# motordriver-v4_0_stspin.net
KiCad netlist of a schematic drawn in Altium Designer
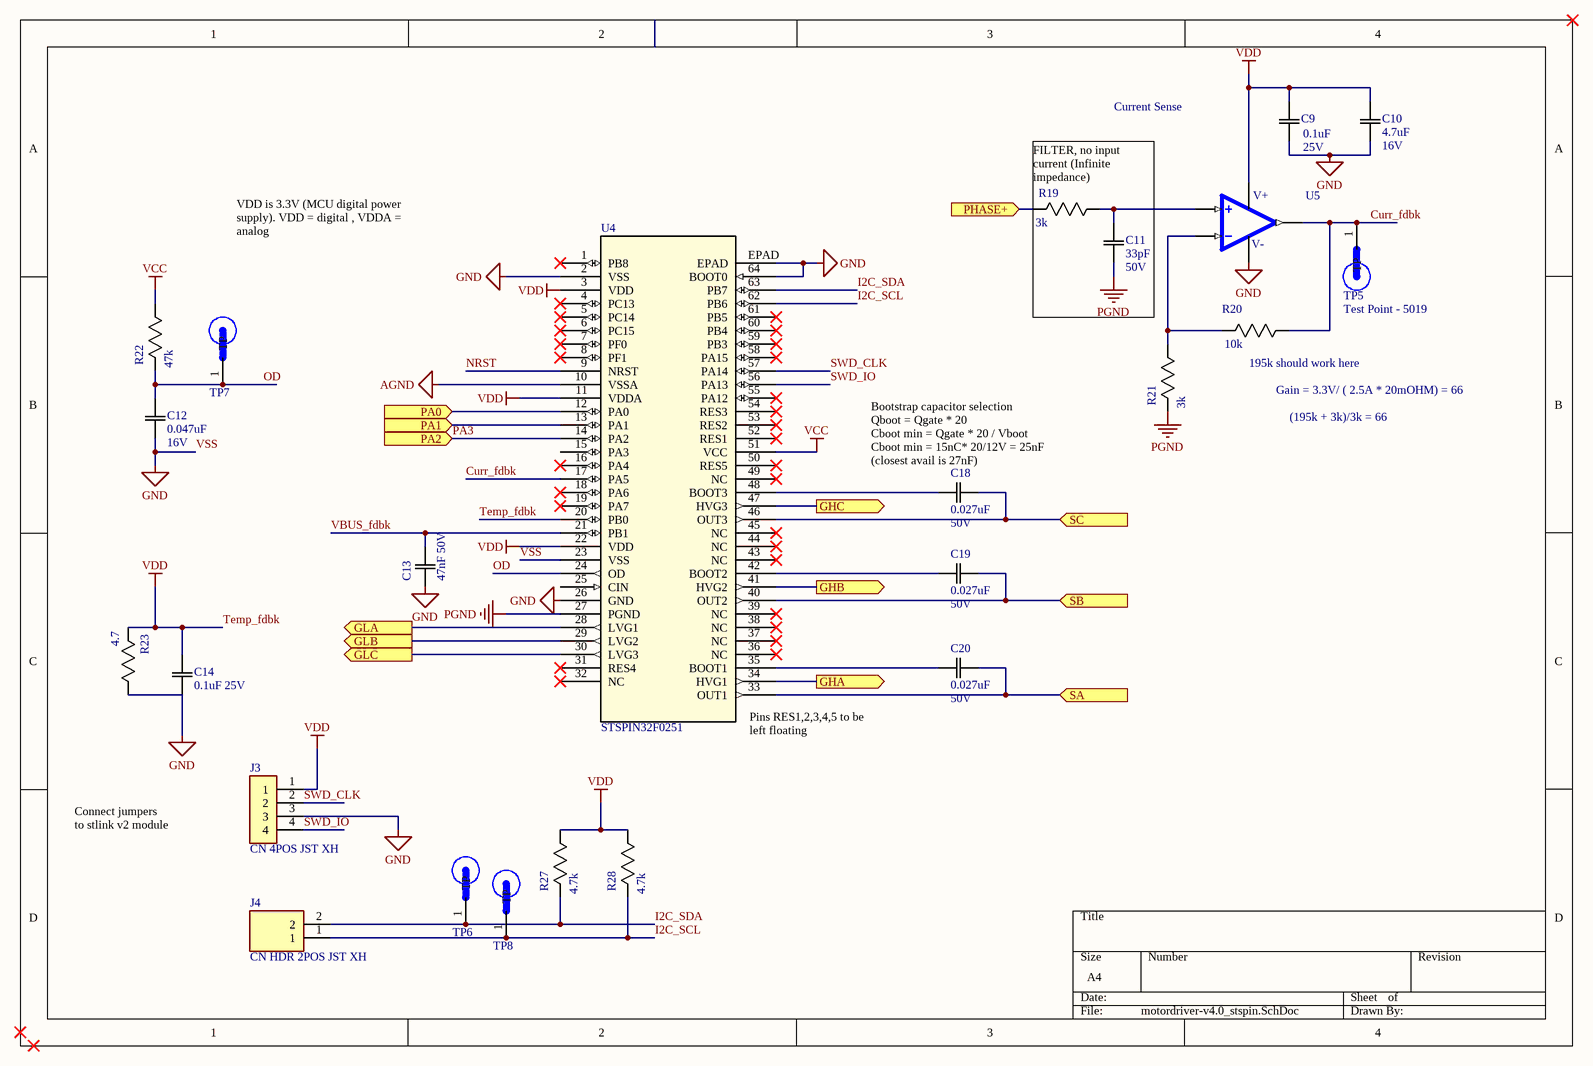
[diagram p0: motordriver-v4.0_stspin.SchDoc]

(export (version "E")
  (design (tool "Eeschema 10.0.6"))
  (components
    (comp (ref "C9")
      (value "0.1uF")
      (footprint "0805")
      (description "CAP CER 0.1UF 25V X7R 0805")
      (fields
        (field (name "TOLERANCE") "10%")
        (field (name "RATING") "25V")
        (field (name "Comment") "0.1uF 25V")
      )
      (libsource (lib "AltiumLibraries") (part "CAP 0.1uF 25V"))
    )
    (comp (ref "C10")
      (value "4.7uF")
      (footprint "0603")
      (description "CAP CER 4.7UF 16V X5R 0603/0805")
      (fields (field (name "TOLERANCE") "10%") (field (name "RATING") "16V"))
      (libsource (lib "AltiumLibraries") (part "CAP 4.7uF 16V"))
    )
    (comp (ref "C11")
      (value "33pF")
      (footprint "0603")
      (description "CAP CER 33PF 50V X7R 0603/0805")
      (fields (field (name "TOLERANCE") "10%") (field (name "RATING") "50V"))
      (libsource (lib "AltiumLibraries") (part "CAP 33pF 50V"))
    )
    (comp (ref "C12")
      (value "0.047uF")
      (footprint "0603")
      (description "CAP CER 0.047UF 16V X5R 0603/0805")
      (fields (field (name "TOLERANCE") "10%") (field (name "RATING") "16V"))
      (libsource (lib "AltiumLibraries") (part "CAP 0.047uF 16V"))
    )
    (comp (ref "C13")
      (value "47nF 50V")
      (footprint "0805")
      (description "CAP CER 0.047UF 50V X7R 0805")
      (fields (field (name "TOLERANCE") "5%"))
      (libsource (lib "AltiumLibraries") (part "CAP 47nF 50V"))
    )
    (comp (ref "C14")
      (value "0.1uF 25V")
      (footprint "0805")
      (description "CAP CER 0.1UF 25V X7R 0805")
      (fields (field (name "TOLERANCE") "10%"))
      (libsource (lib "AltiumLibraries") (part "CAP 0.1uF 25V"))
    )
    (comp (ref "C18")
      (value "0.027uF")
      (footprint "0805")
      (description "CAP CER 0.027UF 50V X7R 0805")
      (fields (field (name "TOLERANCE") "5%") (field (name "RATING") "50V"))
      (libsource (lib "AltiumLibraries") (part "CAP 0.027UF 50V X7R 0805"))
    )
    (comp (ref "C19")
      (value "0.027uF")
      (footprint "0805")
      (description "CAP CER 0.027UF 50V X7R 0805")
      (fields (field (name "TOLERANCE") "5%") (field (name "RATING") "50V"))
      (libsource (lib "AltiumLibraries") (part "CAP 0.027UF 50V X7R 0805"))
    )
    (comp (ref "C20")
      (value "0.027uF")
      (footprint "0805")
      (description "CAP CER 0.027UF 50V X7R 0805")
      (fields (field (name "TOLERANCE") "5%") (field (name "RATING") "50V"))
      (libsource (lib "AltiumLibraries") (part "CAP 0.027UF 50V X7R 0805"))
    )
    (comp (ref "J3")
      (value "CN 4POS JST XH")
      (footprint "JST_B4B-XH-A(LF)(SN)")
      (description "Connector Header Through Hole 4 position 0.098 _2.50mm_\r\nB4B-XH-A(LF)(SN)")
      (fields (field (name "MP") "B4B-XH-A_LF__SN_") (field (name "MF") "JST Sales"))
      (libsource (lib "AltiumLibraries") (part "CN 4POS JST XH"))
    )
    (comp (ref "J4")
      (value "CN HDR 2POS JST XH")
      (footprint "JST_B2B-XH-A(LF)(SN)")
      (description "Connector Header Through Hole 2 position 0.098 _2.50mm_\r\nJST XH")
      (fields (field (name "MP") "B2B-XH-A_LF__SN_") (field (name "MF") "JST Sales"))
      (libsource (lib "AltiumLibraries") (part "CN HDR 2POS JST XH"))
    )
    (comp (ref "R19")
      (value "3k")
      (footprint "0805")
      (description "RES SMD 3K OHM 5% 1/8W 0805")
      (fields (field (name "TOLERANCE") "5%"))
      (libsource (lib "AltiumLibraries") (part "RES 3k 1/8W"))
    )
    (comp (ref "R20")
      (value "10k")
      (footprint "0805")
      (description "RES SMD 10K OHM 5% 1/8W 0805")
      (fields (field (name "TOLERANCE") "5%"))
      (libsource (lib "AltiumLibraries") (part "RES 10k 1/8W - 5%"))
    )
    (comp (ref "R21")
      (value "3k")
      (footprint "0805")
      (description "RES SMD 3K OHM 5% 1/8W 0805")
      (fields (field (name "TOLERANCE") "5%"))
      (libsource (lib "AltiumLibraries") (part "RES 3k 1/8W"))
    )
    (comp (ref "R22")
      (value "47k")
      (footprint "0805")
      (description "RES SMD 47k OHM 5% 1/8W 0805")
      (fields (field (name "TOLERANCE") "5%"))
      (libsource (lib "AltiumLibraries") (part "RES 47k 1/8W - 5%"))
    )
    (comp (ref "R23")
      (value "4.7")
      (footprint "0805")
      (description "RES SMD 4.7 OHM 5% 1/8W 0805")
      (fields (field (name "TOLERANCE") "5%"))
      (libsource (lib "AltiumLibraries") (part "RES 4.7 1/8W"))
    )
    (comp (ref "R27")
      (value "4.7k")
      (footprint "0805")
      (description "RES SMD 4.7k OHM 1% 1/8W 0805")
      (fields (field (name "TOLERANCE") "1%"))
      (libsource (lib "AltiumLibraries") (part "RES 4.7k 1/8W - 1%"))
    )
    (comp (ref "R28")
      (value "4.7k")
      (footprint "0805")
      (description "RES SMD 4.7k OHM 1% 1/8W 0805")
      (fields (field (name "TOLERANCE") "1%"))
      (libsource (lib "AltiumLibraries") (part "RES 4.7k 1/8W - 1%"))
    )
    (comp (ref "TP5")
      (value "Test Point - 5019")
      (footprint "TP380X203")
      (description "PC Test Point, Miniature Phosphor Bronze, Silver Plating Surface Mount Mounting Type")
      (fields (field (name "MP") "5019") (field (name "MF") "Keystone Electronics"))
      (libsource (lib "AltiumLibraries") (part "Test Point - 5019"))
    )
    (comp (ref "TP6")
      (value "Test Point - 5019")
      (footprint "TP380X203")
      (description "PC Test Point, Miniature Phosphor Bronze, Silver Plating Surface Mount Mounting Type")
      (fields (field (name "MP") "5019") (field (name "MF") "Keystone Electronics"))
      (libsource (lib "AltiumLibraries") (part "Test Point - 5019"))
    )
    (comp (ref "TP7")
      (value "Test Point - 5019")
      (footprint "TP380X203")
      (description "PC Test Point, Miniature Phosphor Bronze, Silver Plating Surface Mount Mounting Type")
      (fields (field (name "MP") "5019") (field (name "MF") "Keystone Electronics"))
      (libsource (lib "AltiumLibraries") (part "Test Point - 5019"))
    )
    (comp (ref "TP8")
      (value "Test Point - 5019")
      (footprint "TP380X203")
      (description "PC Test Point, Miniature Phosphor Bronze, Silver Plating Surface Mount Mounting Type")
      (fields (field (name "MP") "5019") (field (name "MF") "Keystone Electronics"))
      (libsource (lib "AltiumLibraries") (part "Test Point - 5019"))
    )
    (comp (ref "U4")
      (value "STSPIN32F0251")
      (footprint "STSPIN32F0251TR")
      (description "250 V BLDC THREE-PHASE CONTROLLER")
      (fields (field (name "MANUFACTURER") "STMicroelectronics"))
      (libsource (lib "AltiumLibraries") (part "STSPIN32F0251"))
    )
    (comp (ref "U5")
      (value "OP AMP TSV911ILT")
      (footprint "TSV911ILT Opamp")
      (description "IC OPAMP GP 1 CIRCUIT SOT23-5")
      (fields (field (name "MANUFACTURER") "STMicroelectronics"))
      (libsource (lib "AltiumLibraries") (part "OP AMP TSV911ILT"))
    )
  )
  (nets
    (net (code "1") (name "/Curr_fdbk") (class "Default")
      (node (ref "R20") (pin "1") (pinfunction "R1_1") (pintype "passive"))
      (node (ref "TP5") (pin "1") (pinfunction "TP_1") (pintype "passive"))
      (node (ref "U4") (pin "17") (pinfunction "PA5_17") (pintype "bidirectional"))
      (node (ref "U5") (pin "1") (pinfunction "OUT_1") (pintype "output"))
    )
    (net (code "2") (name "/GHA") (class "Default")
      (node (ref "U4") (pin "34") (pinfunction "HVG1_34") (pintype "output"))
    )
    (net (code "3") (name "/GHB") (class "Default")
      (node (ref "U4") (pin "41") (pinfunction "HVG2_41") (pintype "output"))
    )
    (net (code "4") (name "/GHC") (class "Default")
      (node (ref "U4") (pin "47") (pinfunction "HVG3_47") (pintype "output"))
    )
    (net (code "5") (name "/GLA") (class "Default")
      (node (ref "U4") (pin "28") (pinfunction "LVG1_28") (pintype "output"))
    )
    (net (code "6") (name "/GLB") (class "Default")
      (node (ref "U4") (pin "29") (pinfunction "LVG2_29") (pintype "output"))
    )
    (net (code "7") (name "/GLC") (class "Default")
      (node (ref "U4") (pin "30") (pinfunction "LVG3_30") (pintype "output"))
    )
    (net (code "8") (name "/I2C_SCL") (class "Default")
      (node (ref "J4") (pin "1") (pinfunction "1_1") (pintype "passive"))
      (node (ref "R28") (pin "2") (pinfunction "R2_2") (pintype "passive"))
      (node (ref "TP8") (pin "1") (pinfunction "TP_1") (pintype "passive"))
      (node (ref "U4") (pin "62") (pinfunction "PB6_62") (pintype "bidirectional"))
    )
    (net (code "9") (name "/I2C_SDA") (class "Default")
      (node (ref "J4") (pin "2") (pinfunction "2_2") (pintype "passive"))
      (node (ref "R27") (pin "2") (pinfunction "R2_2") (pintype "passive"))
      (node (ref "TP6") (pin "1") (pinfunction "TP_1") (pintype "passive"))
      (node (ref "U4") (pin "63") (pinfunction "PB7_63") (pintype "bidirectional"))
    )
    (net (code "10") (name "/NRST") (class "Default")
      (node (ref "U4") (pin "9") (pinfunction "NRST_9") (pintype "passive"))
    )
    (net (code "11") (name "/OD") (class "Default")
      (node (ref "C12") (pin "2") (pinfunction "C2_2") (pintype "passive"))
      (node (ref "R22") (pin "2") (pinfunction "R2_2") (pintype "passive"))
      (node (ref "TP7") (pin "1") (pinfunction "TP_1") (pintype "passive"))
      (node (ref "U4") (pin "24") (pinfunction "OD_24") (pintype "output"))
    )
    (net (code "12") (name "/PA0") (class "Default")
      (node (ref "U4") (pin "12") (pinfunction "PA0_12") (pintype "bidirectional"))
    )
    (net (code "13") (name "/PA1") (class "Default")
      (node (ref "U4") (pin "13") (pinfunction "PA1_13") (pintype "bidirectional"))
    )
    (net (code "14") (name "/PA3") (class "Default")
      (node (ref "U4") (pin "14") (pinfunction "PA2_14") (pintype "bidirectional"))
    )
    (net (code "15") (name "/PHASE+") (class "Default")
      (node (ref "R19") (pin "2") (pinfunction "R2_2") (pintype "passive"))
    )
    (net (code "16") (name "/SA") (class "Default")
      (node (ref "C20") (pin "2") (pinfunction "2_2") (pintype "passive"))
      (node (ref "U4") (pin "33") (pinfunction "OUT1_33") (pintype "output"))
    )
    (net (code "17") (name "/SB") (class "Default")
      (node (ref "C19") (pin "2") (pinfunction "2_2") (pintype "passive"))
      (node (ref "U4") (pin "40") (pinfunction "OUT2_40") (pintype "output"))
    )
    (net (code "18") (name "/SC") (class "Default")
      (node (ref "C18") (pin "2") (pinfunction "2_2") (pintype "passive"))
      (node (ref "U4") (pin "46") (pinfunction "OUT3_46") (pintype "output"))
    )
    (net (code "19") (name "/SWD_CLK") (class "Default")
      (node (ref "J3") (pin "2") (pinfunction "2_2") (pintype "passive"))
      (node (ref "U4") (pin "57") (pinfunction "PA14_57") (pintype "bidirectional"))
    )
    (net (code "20") (name "/SWD_IO") (class "Default")
      (node (ref "J3") (pin "4") (pinfunction "4_4") (pintype "passive"))
      (node (ref "U4") (pin "56") (pinfunction "PA13_56") (pintype "bidirectional"))
    )
    (net (code "21") (name "/VBUS_fdbk") (class "Default")
      (node (ref "C13") (pin "2") (pinfunction "C2_2") (pintype "passive"))
      (node (ref "U4") (pin "21") (pinfunction "PB1_21") (pintype "bidirectional"))
    )
    (net (code "22") (name "AGND") (class "Default")
      (node (ref "U4") (pin "10") (pinfunction "VSSA_10") (pintype "passive"))
    )
    (net (code "23") (name "GND") (class "Default")
      (node (ref "C10") (pin "1") (pinfunction "C1_1") (pintype "passive"))
      (node (ref "C12") (pin "1") (pinfunction "C1_1") (pintype "passive"))
      (node (ref "C13") (pin "1") (pinfunction "C1_1") (pintype "passive"))
      (node (ref "C14") (pin "1") (pinfunction "C1_1") (pintype "passive"))
      (node (ref "C9") (pin "1") (pinfunction "C1_1") (pintype "passive"))
      (node (ref "J3") (pin "3") (pinfunction "3_3") (pintype "passive"))
      (node (ref "R23") (pin "1") (pinfunction "R1_1") (pintype "passive"))
      (node (ref "U4") (pin "2") (pinfunction "VSS_2") (pintype "passive"))
      (node (ref "U4") (pin "23") (pinfunction "VSS_23") (pintype "passive"))
      (node (ref "U4") (pin "26") (pinfunction "GND_26") (pintype "passive"))
      (node (ref "U4") (pin "64") (pinfunction "BOOT0_64") (pintype "input"))
      (node (ref "U4") (pin "EPAD") (pinfunction "EPAD_EPAD") (pintype "passive"))
      (node (ref "U5") (pin "2") (pinfunction "V-_2") (pintype "power_in"))
    )
    (net (code "24") (name "Net-(C11-C2)") (class "Default")
      (node (ref "C11") (pin "2") (pinfunction "C2_2") (pintype "passive"))
      (node (ref "R19") (pin "1") (pinfunction "R1_1") (pintype "passive"))
      (node (ref "U5") (pin "3") (pinfunction "IN+_3") (pintype "input"))
    )
    (net (code "25") (name "Net-(R20-R2)") (class "Default")
      (node (ref "R20") (pin "2") (pinfunction "R2_2") (pintype "passive"))
      (node (ref "R21") (pin "1") (pinfunction "R1_1") (pintype "passive"))
      (node (ref "U5") (pin "4") (pinfunction "IN-_4") (pintype "input"))
    )
    (net (code "26") (name "Net-(U4-BOOT1)") (class "Default")
      (node (ref "C20") (pin "1") (pinfunction "1_1") (pintype "passive"))
      (node (ref "U4") (pin "35") (pinfunction "BOOT1_35") (pintype "power_in"))
    )
    (net (code "27") (name "Net-(U4-BOOT2)") (class "Default")
      (node (ref "C19") (pin "1") (pinfunction "1_1") (pintype "passive"))
      (node (ref "U4") (pin "42") (pinfunction "BOOT2_42") (pintype "power_in"))
    )
    (net (code "28") (name "Net-(U4-BOOT3)") (class "Default")
      (node (ref "C18") (pin "1") (pinfunction "1_1") (pintype "passive"))
      (node (ref "U4") (pin "48") (pinfunction "BOOT3_48") (pintype "power_in"))
    )
    (net (code "29") (name "PGND") (class "Default")
      (node (ref "C11") (pin "1") (pinfunction "C1_1") (pintype "passive"))
      (node (ref "R21") (pin "2") (pinfunction "R2_2") (pintype "passive"))
      (node (ref "U4") (pin "27") (pinfunction "PGND_27") (pintype "passive"))
    )
    (net (code "30") (name "VCC") (class "Default")
      (node (ref "R22") (pin "1") (pinfunction "R1_1") (pintype "passive"))
      (node (ref "U4") (pin "51") (pinfunction "VCC_51") (pintype "power_in"))
    )
    (net (code "31") (name "VDD") (class "Default")
      (node (ref "C10") (pin "2") (pinfunction "C2_2") (pintype "passive"))
      (node (ref "C14") (pin "2") (pinfunction "C2_2") (pintype "passive"))
      (node (ref "C9") (pin "2") (pinfunction "C2_2") (pintype "passive"))
      (node (ref "J3") (pin "1") (pinfunction "1_1") (pintype "passive"))
      (node (ref "R23") (pin "2") (pinfunction "R2_2") (pintype "passive"))
      (node (ref "R27") (pin "1") (pinfunction "R1_1") (pintype "passive"))
      (node (ref "R28") (pin "1") (pinfunction "R1_1") (pintype "passive"))
      (node (ref "U4") (pin "11") (pinfunction "VDDA_11") (pintype "power_in"))
      (node (ref "U4") (pin "20") (pinfunction "PB0_20") (pintype "bidirectional"))
      (node (ref "U4") (pin "22") (pinfunction "VDD_22") (pintype "power_in"))
      (node (ref "U4") (pin "3") (pinfunction "VDD_3") (pintype "power_in"))
      (node (ref "U5") (pin "5") (pinfunction "V+_5") (pintype "power_in"))
    )
    (net (code "32") (name "unconnected-(U4-CIN-Pad25)") (class "Default")
      (node (ref "U4") (pin "25") (pinfunction "CIN_25") (pintype "input"))
    )
    (net (code "33") (name "unconnected-(U4-NC-Pad32)") (class "Default")
      (node (ref "U4") (pin "32") (pinfunction "NC_32") (pintype "passive+no_connect"))
    )
    (net (code "34") (name "unconnected-(U4-NC-Pad36)") (class "Default")
      (node (ref "U4") (pin "36") (pinfunction "NC_36") (pintype "passive+no_connect"))
    )
    (net (code "35") (name "unconnected-(U4-NC-Pad37)") (class "Default")
      (node (ref "U4") (pin "37") (pinfunction "NC_37") (pintype "passive+no_connect"))
    )
    (net (code "36") (name "unconnected-(U4-NC-Pad38)") (class "Default")
      (node (ref "U4") (pin "38") (pinfunction "NC_38") (pintype "passive+no_connect"))
    )
    (net (code "37") (name "unconnected-(U4-NC-Pad39)") (class "Default")
      (node (ref "U4") (pin "39") (pinfunction "NC_39") (pintype "passive+no_connect"))
    )
    (net (code "38") (name "unconnected-(U4-NC-Pad43)") (class "Default")
      (node (ref "U4") (pin "43") (pinfunction "NC_43") (pintype "passive+no_connect"))
    )
    (net (code "39") (name "unconnected-(U4-NC-Pad44)") (class "Default")
      (node (ref "U4") (pin "44") (pinfunction "NC_44") (pintype "passive+no_connect"))
    )
    (net (code "40") (name "unconnected-(U4-NC-Pad45)") (class "Default")
      (node (ref "U4") (pin "45") (pinfunction "NC_45") (pintype "passive+no_connect"))
    )
    (net (code "41") (name "unconnected-(U4-NC-Pad49)") (class "Default")
      (node (ref "U4") (pin "49") (pinfunction "NC_49") (pintype "passive+no_connect"))
    )
    (net (code "42") (name "unconnected-(U4-PA3-Pad15)") (class "Default")
      (node (ref "U4") (pin "15") (pinfunction "PA3_15") (pintype "bidirectional"))
    )
    (net (code "43") (name "unconnected-(U4-PA4-Pad16)") (class "Default")
      (node (ref "U4") (pin "16") (pinfunction "PA4_16") (pintype "bidirectional+no_connect"))
    )
    (net (code "44") (name "unconnected-(U4-PA6-Pad18)") (class "Default")
      (node (ref "U4") (pin "18") (pinfunction "PA6_18") (pintype "bidirectional+no_connect"))
    )
    (net (code "45") (name "unconnected-(U4-PA7-Pad19)") (class "Default")
      (node (ref "U4") (pin "19") (pinfunction "PA7_19") (pintype "bidirectional+no_connect"))
    )
    (net (code "46") (name "unconnected-(U4-PA12-Pad55)") (class "Default")
      (node (ref "U4") (pin "55") (pinfunction "PA12_55") (pintype "bidirectional+no_connect"))
    )
    (net (code "47") (name "unconnected-(U4-PA15-Pad58)") (class "Default")
      (node (ref "U4") (pin "58") (pinfunction "PA15_58") (pintype "bidirectional+no_connect"))
    )
    (net (code "48") (name "unconnected-(U4-PB3-Pad59)") (class "Default")
      (node (ref "U4") (pin "59") (pinfunction "PB3_59") (pintype "bidirectional+no_connect"))
    )
    (net (code "49") (name "unconnected-(U4-PB4-Pad60)") (class "Default")
      (node (ref "U4") (pin "60") (pinfunction "PB4_60") (pintype "bidirectional+no_connect"))
    )
    (net (code "50") (name "unconnected-(U4-PB5-Pad61)") (class "Default")
      (node (ref "U4") (pin "61") (pinfunction "PB5_61") (pintype "bidirectional+no_connect"))
    )
    (net (code "51") (name "unconnected-(U4-PB8-Pad1)") (class "Default")
      (node (ref "U4") (pin "1") (pinfunction "PB8_1") (pintype "bidirectional+no_connect"))
    )
    (net (code "52") (name "unconnected-(U4-PC13-Pad4)") (class "Default")
      (node (ref "U4") (pin "4") (pinfunction "PC13_4") (pintype "bidirectional+no_connect"))
    )
    (net (code "53") (name "unconnected-(U4-PC14-Pad5)") (class "Default")
      (node (ref "U4") (pin "5") (pinfunction "PC14_5") (pintype "bidirectional+no_connect"))
    )
    (net (code "54") (name "unconnected-(U4-PC15-Pad6)") (class "Default")
      (node (ref "U4") (pin "6") (pinfunction "PC15_6") (pintype "bidirectional+no_connect"))
    )
    (net (code "55") (name "unconnected-(U4-PF0-Pad7)") (class "Default")
      (node (ref "U4") (pin "7") (pinfunction "PF0_7") (pintype "bidirectional+no_connect"))
    )
    (net (code "56") (name "unconnected-(U4-PF1-Pad8)") (class "Default")
      (node (ref "U4") (pin "8") (pinfunction "PF1_8") (pintype "bidirectional+no_connect"))
    )
    (net (code "57") (name "unconnected-(U4-RES1-Pad52)") (class "Default")
      (node (ref "U4") (pin "52") (pinfunction "RES1_52") (pintype "passive+no_connect"))
    )
    (net (code "58") (name "unconnected-(U4-RES2-Pad53)") (class "Default")
      (node (ref "U4") (pin "53") (pinfunction "RES2_53") (pintype "passive+no_connect"))
    )
    (net (code "59") (name "unconnected-(U4-RES3-Pad54)") (class "Default")
      (node (ref "U4") (pin "54") (pinfunction "RES3_54") (pintype "passive+no_connect"))
    )
    (net (code "60") (name "unconnected-(U4-RES4-Pad31)") (class "Default")
      (node (ref "U4") (pin "31") (pinfunction "RES4_31") (pintype "passive+no_connect"))
    )
    (net (code "61") (name "unconnected-(U4-RES5-Pad50)") (class "Default")
      (node (ref "U4") (pin "50") (pinfunction "RES5_50") (pintype "passive+no_connect"))
    )
  )
)
